# Jar_of_Fireflies_rev_B.net
KiCad netlist of a schematic drawn in EAGLE
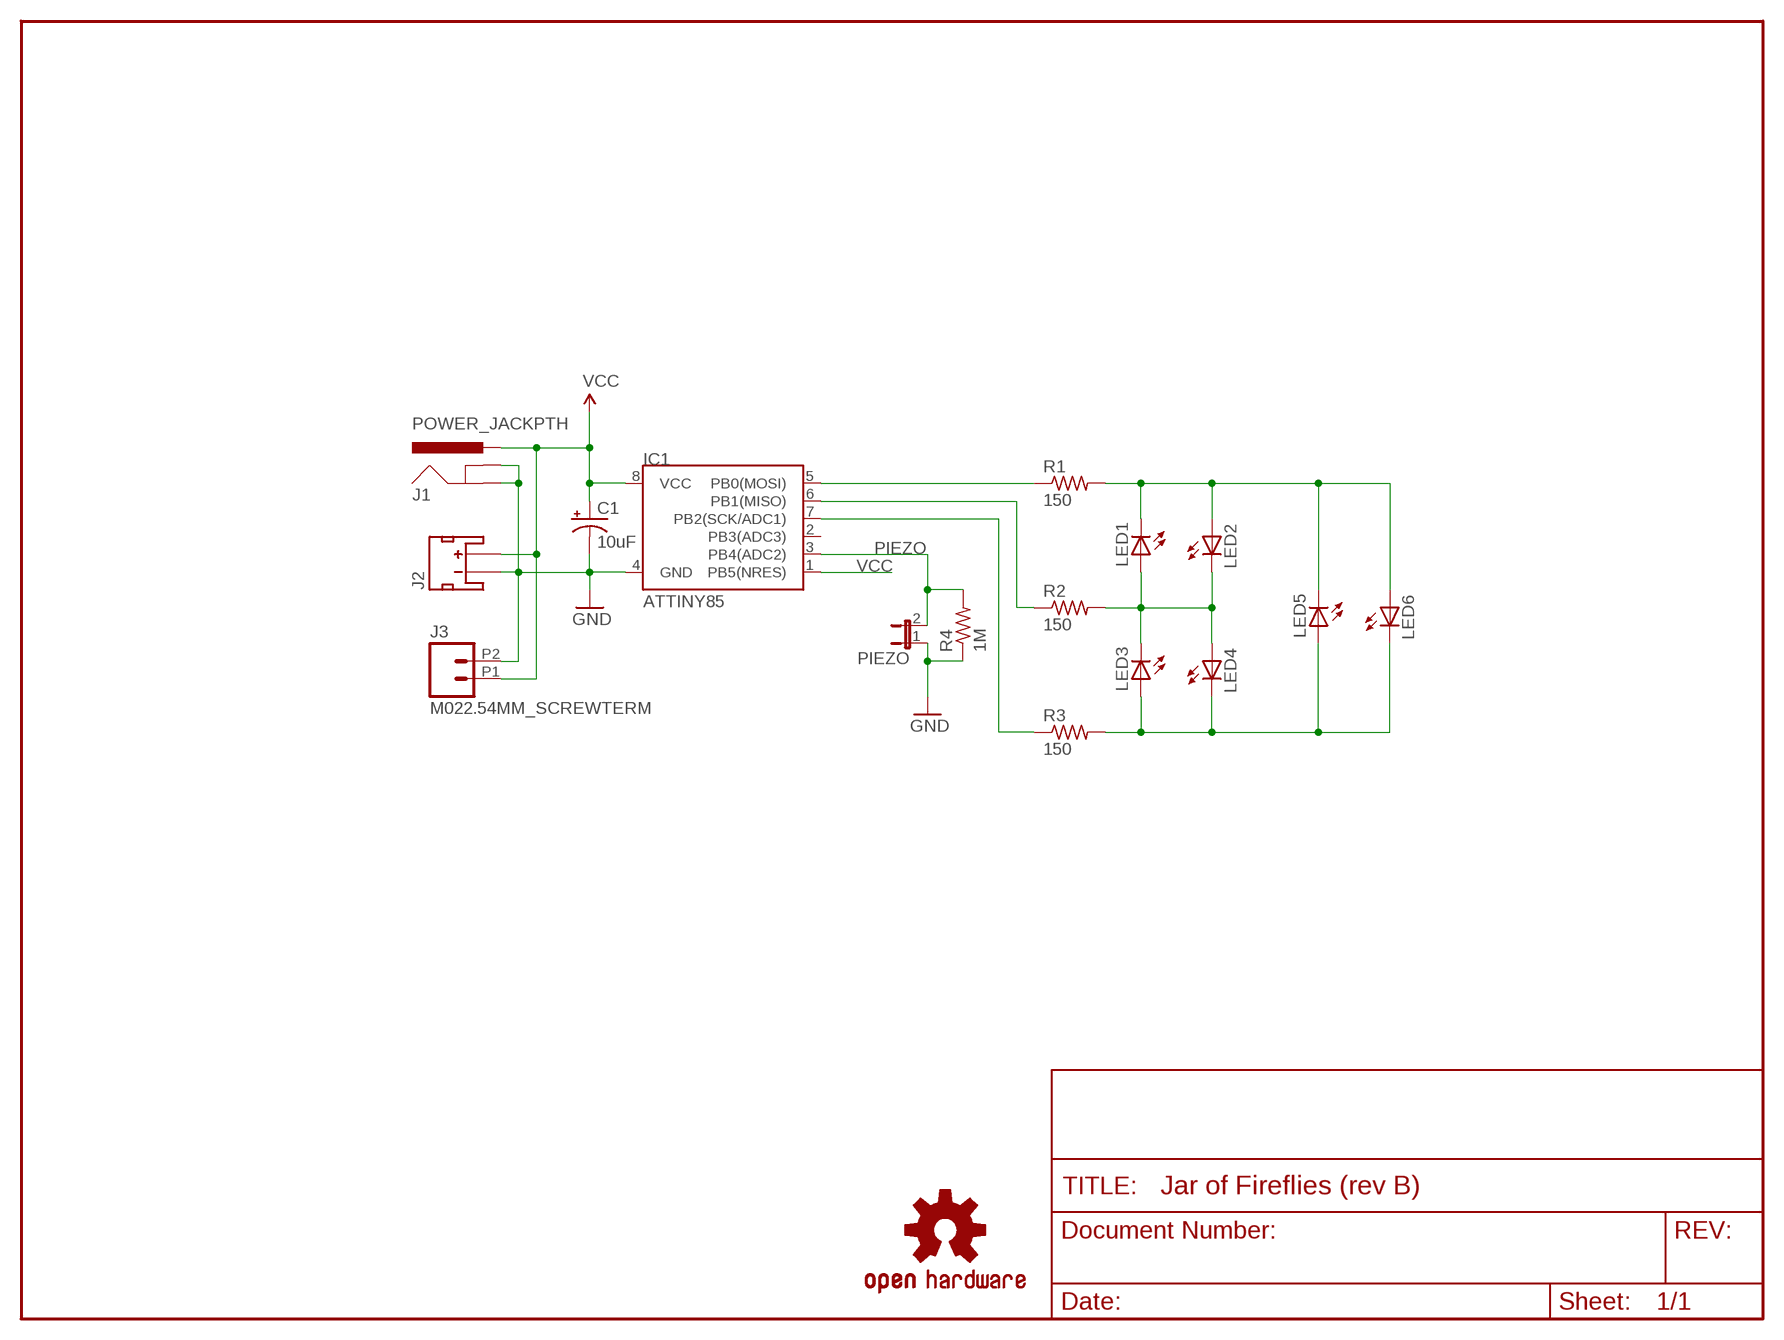
[diagram p0: schematic, sheet 1]

(export (version "E")
  (design (tool "Eeschema 10.0.6"))
  (components
    (comp (ref "C1")
      (value "10uF")
      (footprint "eagle-import:CPOL-RADIAL-10UF-25V")
      (libsource (lib "eagle-import") (part "CAP_POLPTH2"))
    )
    (comp (ref "IC1")
      (value "ATTINY85")
      (footprint "eagle-import:DIP08")
      (libsource (lib "eagle-import") (part "ATTINY45DIP8"))
    )
    (comp (ref "J1")
      (value "POWER_JACKPTH")
      (footprint "eagle-import:POWER_JACK_PTH")
      (libsource (lib "eagle-import") (part "POWER_JACKPTH"))
    )
    (comp (ref "J2")
      (value "JST_2MM_MALE")
      (footprint "eagle-import:JST-2-SMD")
      (libsource (lib "eagle-import") (part "JST_2MM_MALE"))
    )
    (comp (ref "J3")
      (value "M022.54MM_SCREWTERM")
      (footprint "eagle-import:1X02_2.54_SCREWTERM")
      (libsource (lib "eagle-import") (part "M022.54MM_SCREWTERM"))
    )
    (comp (ref "LED1")
      (value "LED5MM")
      (footprint "eagle-import:LED5MM")
      (libsource (lib "eagle-import") (part "LED5MM"))
    )
    (comp (ref "LED2")
      (value "LED5MM")
      (footprint "eagle-import:LED5MM")
      (libsource (lib "eagle-import") (part "LED5MM"))
    )
    (comp (ref "LED3")
      (value "LED5MM")
      (footprint "eagle-import:LED5MM")
      (libsource (lib "eagle-import") (part "LED5MM"))
    )
    (comp (ref "LED4")
      (value "LED5MM")
      (footprint "eagle-import:LED5MM")
      (libsource (lib "eagle-import") (part "LED5MM"))
    )
    (comp (ref "LED5")
      (value "LED5MM")
      (footprint "eagle-import:LED5MM")
      (libsource (lib "eagle-import") (part "LED5MM"))
    )
    (comp (ref "LED6")
      (value "LED5MM")
      (footprint "eagle-import:LED5MM")
      (libsource (lib "eagle-import") (part "LED5MM"))
    )
    (comp (ref "LOGO1")
      (value "OSHW-LOGOL")
      (footprint "eagle-import:OSHW-LOGO-L")
      (libsource (lib "eagle-import") (part "OSHW-LOGOL"))
    )
    (comp (ref "PIEZO")
      (value "JUMPER-2PTH")
      (footprint "eagle-import:1X02")
      (libsource (lib "eagle-import") (part "JUMPER-2PTH"))
    )
    (comp (ref "R1")
      (value "150")
      (footprint "eagle-import:0207_2V")
      (libsource (lib "eagle-import") (part "R-US_0207/2V"))
    )
    (comp (ref "R2")
      (value "150")
      (footprint "eagle-import:0204_7")
      (libsource (lib "eagle-import") (part "R-US_0204/7"))
    )
    (comp (ref "R3")
      (value "150")
      (footprint "eagle-import:0207_2V")
      (libsource (lib "eagle-import") (part "R-US_0207/2V"))
    )
    (comp (ref "R4")
      (value "1M")
      (footprint "eagle-import:0204_7")
      (libsource (lib "eagle-import") (part "R-US_0204/7"))
    )
  )
  (nets
    (net (code "1") (name "/PIEZO") (class "Default")
      (node (ref "IC1") (pin "3") (pinfunction "PB4(ADC2)_3") (pintype "bidirectional"))
      (node (ref "PIEZO") (pin "2") (pinfunction "2_2") (pintype "passive"))
      (node (ref "R4") (pin "2") (pinfunction "2_2") (pintype "passive"))
    )
    (net (code "2") (name "GND") (class "Default")
      (node (ref "C1") (pin "2") (pinfunction "-_2") (pintype "passive"))
      (node (ref "IC1") (pin "4") (pinfunction "GND_4") (pintype "bidirectional"))
      (node (ref "J1") (pin "GND") (pinfunction "GND_GND") (pintype "bidirectional"))
      (node (ref "J1") (pin "GNDBREAK") (pinfunction "GNDBREAK_GNDBREAK") (pintype "bidirectional"))
      (node (ref "J2") (pin "1") (pinfunction "-_1") (pintype "bidirectional"))
      (node (ref "J3") (pin "P2") (pinfunction "2_P2") (pintype "passive"))
      (node (ref "PIEZO") (pin "1") (pinfunction "1_1") (pintype "passive"))
      (node (ref "R4") (pin "1") (pinfunction "1_1") (pintype "passive"))
    )
    (net (code "3") (name "Net-(IC1-PB0(MOSI))") (class "Default")
      (node (ref "IC1") (pin "5") (pinfunction "PB0(MOSI)_5") (pintype "bidirectional"))
      (node (ref "R1") (pin "1") (pinfunction "1_1") (pintype "passive"))
    )
    (net (code "4") (name "Net-(IC1-PB1(MISO))") (class "Default")
      (node (ref "IC1") (pin "6") (pinfunction "PB1(MISO)_6") (pintype "bidirectional"))
      (node (ref "R2") (pin "1") (pinfunction "1_1") (pintype "passive"))
    )
    (net (code "5") (name "Net-(IC1-PB2(SCK{slash}ADC1))") (class "Default")
      (node (ref "IC1") (pin "7") (pinfunction "PB2(SCK/ADC1)_7") (pintype "bidirectional"))
      (node (ref "R3") (pin "1") (pinfunction "1_1") (pintype "passive"))
    )
    (net (code "6") (name "Net-(LED1-C)") (class "Default")
      (node (ref "LED1") (pin "K") (pinfunction "C_K") (pintype "passive"))
      (node (ref "LED2") (pin "A") (pinfunction "A_A") (pintype "passive"))
      (node (ref "LED5") (pin "K") (pinfunction "C_K") (pintype "passive"))
      (node (ref "LED6") (pin "A") (pinfunction "A_A") (pintype "passive"))
      (node (ref "R1") (pin "2") (pinfunction "2_2") (pintype "passive"))
    )
    (net (code "7") (name "Net-(LED2-C)") (class "Default")
      (node (ref "LED1") (pin "A") (pinfunction "A_A") (pintype "passive"))
      (node (ref "LED2") (pin "K") (pinfunction "C_K") (pintype "passive"))
      (node (ref "LED3") (pin "K") (pinfunction "C_K") (pintype "passive"))
      (node (ref "LED4") (pin "A") (pinfunction "A_A") (pintype "passive"))
      (node (ref "R2") (pin "2") (pinfunction "2_2") (pintype "passive"))
    )
    (net (code "8") (name "Net-(LED4-C)") (class "Default")
      (node (ref "LED3") (pin "A") (pinfunction "A_A") (pintype "passive"))
      (node (ref "LED4") (pin "K") (pinfunction "C_K") (pintype "passive"))
      (node (ref "LED5") (pin "A") (pinfunction "A_A") (pintype "passive"))
      (node (ref "LED6") (pin "K") (pinfunction "C_K") (pintype "passive"))
      (node (ref "R3") (pin "2") (pinfunction "2_2") (pintype "passive"))
    )
    (net (code "9") (name "VCC") (class "Default")
      (node (ref "C1") (pin "1") (pinfunction "+_1") (pintype "passive"))
      (node (ref "IC1") (pin "1") (pinfunction "PB5(NRES)_1") (pintype "bidirectional"))
      (node (ref "IC1") (pin "8") (pinfunction "VCC_8") (pintype "bidirectional"))
      (node (ref "J1") (pin "PWR") (pinfunction "PWR_PWR") (pintype "bidirectional"))
      (node (ref "J2") (pin "2") (pinfunction "+_2") (pintype "bidirectional"))
      (node (ref "J3") (pin "P1") (pinfunction "1_P1") (pintype "passive"))
    )
    (net (code "10") (name "unconnected-(IC1-PB3(ADC3)-Pad2)") (class "Default")
      (node (ref "IC1") (pin "2") (pinfunction "PB3(ADC3)_2") (pintype "bidirectional"))
    )
    (net (code "11") (name "unconnected-(J2-PAD1-PadNC1)") (class "Default")
      (node (ref "J2") (pin "NC1") (pinfunction "PAD1_NC1") (pintype "bidirectional"))
    )
    (net (code "12") (name "unconnected-(J2-PAD2-PadNC2)") (class "Default")
      (node (ref "J2") (pin "NC2") (pinfunction "PAD2_NC2") (pintype "bidirectional"))
    )
  )
)
